# icp_lm2596.net
KiCad netlist of a schematic drawn in EAGLE
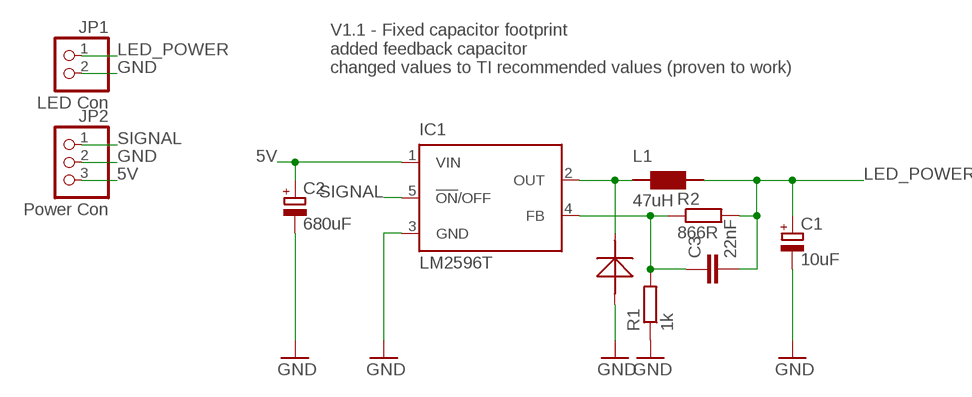
[diagram p0: schematic, sheet 1]

(export (version "E")
  (design (tool "Eeschema 10.0.6"))
  (components
    (comp (ref "C1")
      (value "10uF")
      (footprint "eagle-import:E2,5-7")
      (libsource (lib "eagle-import") (part "CPOL-EUE2.5-7"))
    )
    (comp (ref "C2")
      (value "680uF")
      (footprint "eagle-import:E3,5-8")
      (libsource (lib "eagle-import") (part "CPOL-EUE3.5-8"))
    )
    (comp (ref "C3")
      (value "22nF")
      (footprint "eagle-import:C0805")
      (libsource (lib "eagle-import") (part "C-EUC0805"))
    )
    (comp (ref "D1")
      (value "SB 550")
      (footprint "eagle-import:DO-201-6X")
      (libsource (lib "eagle-import") (part "DIODERM15.24"))
    )
    (comp (ref "IC1")
      (value "LM2596T")
      (footprint "eagle-import:T05D")
      (fields (field (name "MPN") "LM2596T-ADJ/LF02"))
      (libsource (lib "eagle-import") (part "LM2596T"))
    )
    (comp (ref "JP1")
      (value "LED Con")
      (footprint "eagle-import:1X02")
      (libsource (lib "eagle-import") (part "PINHD-1X2"))
    )
    (comp (ref "JP2")
      (value "Power Con")
      (footprint "eagle-import:1X03")
      (libsource (lib "eagle-import") (part "PINHD-1X3"))
    )
    (comp (ref "L1")
      (value "47uH")
      (footprint "eagle-import:PISM")
      (libsource (lib "eagle-import") (part "POWER_INDUCTOR"))
    )
    (comp (ref "R1")
      (value "1k")
      (footprint "eagle-import:0207_2V")
      (libsource (lib "eagle-import") (part "R-EU_0207/2V"))
    )
    (comp (ref "R2")
      (value "866R")
      (footprint "eagle-import:0207_2V")
      (libsource (lib "eagle-import") (part "R-EU_0207/2V"))
    )
  )
  (nets
    (net (code "1") (name "/5V") (class "Default")
      (node (ref "C2") (pin "+") (pinfunction "+_+") (pintype "passive"))
      (node (ref "IC1") (pin "1") (pinfunction "VIN_1") (pintype "input"))
      (node (ref "JP2") (pin "3") (pinfunction "3_3") (pintype "passive"))
    )
    (net (code "2") (name "/LED_POWER") (class "Default")
      (node (ref "C1") (pin "+") (pinfunction "+_+") (pintype "passive"))
      (node (ref "C3") (pin "2") (pinfunction "2_2") (pintype "passive"))
      (node (ref "JP1") (pin "1") (pinfunction "1_1") (pintype "passive"))
      (node (ref "L1") (pin "P$2") (pinfunction "P$2_P$2") (pintype "passive"))
      (node (ref "R2") (pin "2") (pinfunction "2_2") (pintype "passive"))
    )
    (net (code "3") (name "/SIGNAL") (class "Default")
      (node (ref "IC1") (pin "5") (pinfunction "~{ON}/OFF_5") (pintype "input"))
      (node (ref "JP2") (pin "1") (pinfunction "1_1") (pintype "passive"))
    )
    (net (code "4") (name "GND") (class "Default")
      (node (ref "C1") (pin "-") (pinfunction "-_-") (pintype "passive"))
      (node (ref "C2") (pin "-") (pinfunction "-_-") (pintype "passive"))
      (node (ref "D1") (pin "P$1") (pinfunction "A_P$1") (pintype "passive"))
      (node (ref "IC1") (pin "3") (pinfunction "GND_3") (pintype "power_in"))
      (node (ref "JP1") (pin "2") (pinfunction "2_2") (pintype "passive"))
      (node (ref "JP2") (pin "2") (pinfunction "2_2") (pintype "passive"))
      (node (ref "R1") (pin "1") (pinfunction "1_1") (pintype "passive"))
    )
    (net (code "5") (name "Net-(D1-C)") (class "Default")
      (node (ref "D1") (pin "P$2") (pinfunction "C_P$2") (pintype "passive"))
      (node (ref "IC1") (pin "2") (pinfunction "OUT_2") (pintype "output"))
      (node (ref "L1") (pin "P$1") (pinfunction "P$1_P$1") (pintype "passive"))
    )
    (net (code "6") (name "Net-(IC1-FB)") (class "Default")
      (node (ref "C3") (pin "1") (pinfunction "1_1") (pintype "passive"))
      (node (ref "IC1") (pin "4") (pinfunction "FB_4") (pintype "input"))
      (node (ref "R1") (pin "2") (pinfunction "2_2") (pintype "passive"))
      (node (ref "R2") (pin "1") (pinfunction "1_1") (pintype "passive"))
    )
  )
)
